# power_electronics4.net
KiCad netlist of a schematic drawn in EAGLE
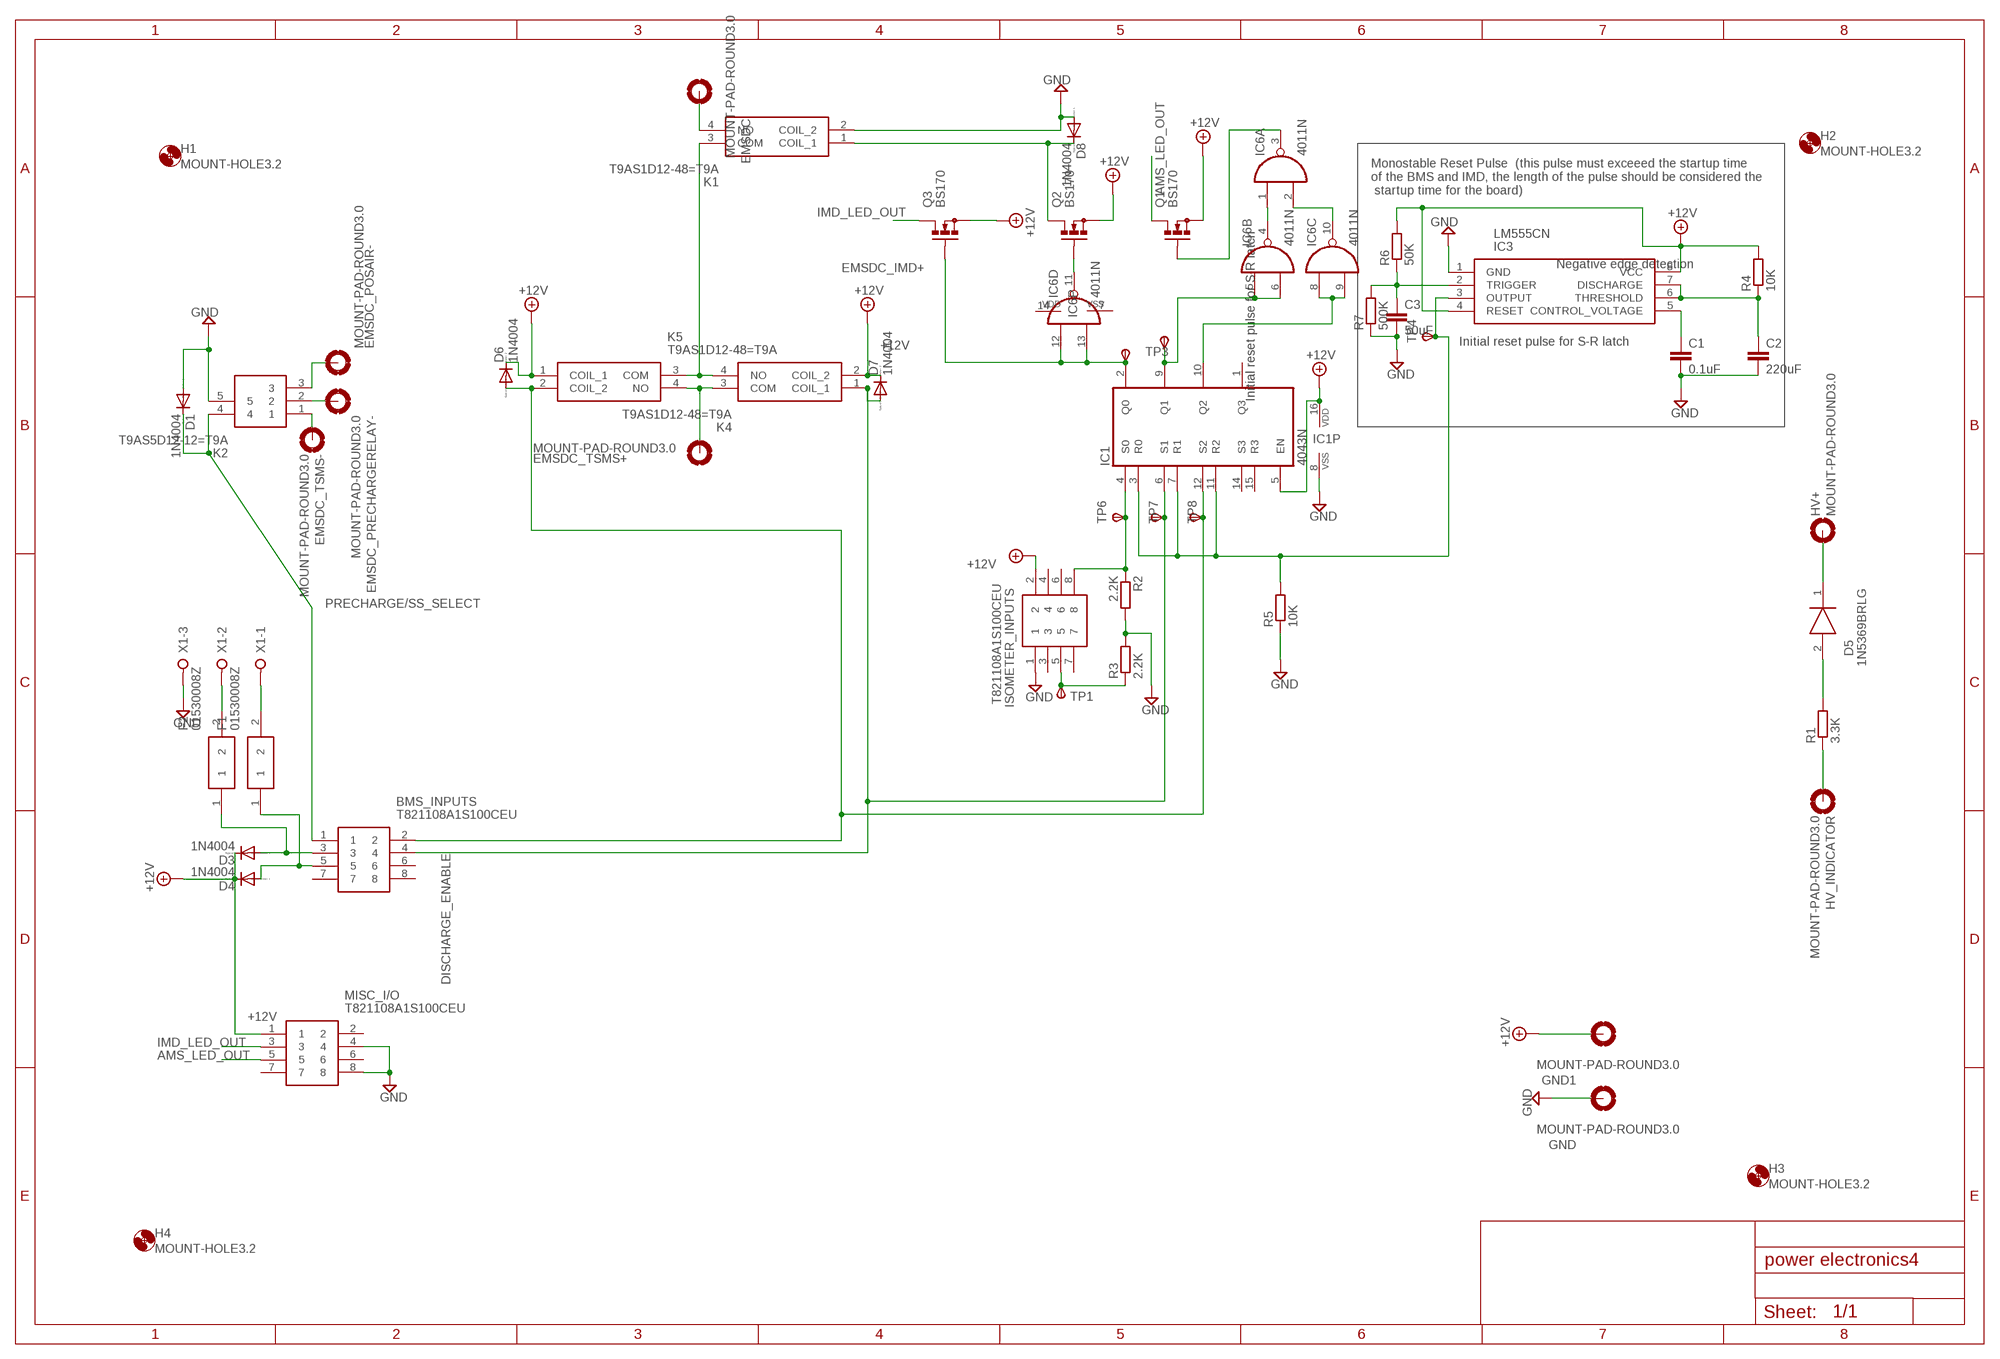
[diagram p0: schematic, sheet 1]

(export (version "E")
  (design (tool "Eeschema 10.0.6"))
  (components
    (comp (ref "BMS_INPUTS")
      (value "T821108A1S100CEU")
      (footprint "eagle-import:HDRV8W64P254_2X4_1778X895X915P")
      (fields (field (name "RS_PART_NUMBER") "8323569"))
      (libsource (lib "eagle-import") (part "T821108A1S100CEU"))
    )
    (comp (ref "C1")
      (value "0.1uF")
      (footprint "eagle-import:C050-024X044")
      (libsource (lib "eagle-import") (part "C-EU050-024X044"))
    )
    (comp (ref "C2")
      (value "220uF")
      (footprint "eagle-import:C050-024X044")
      (libsource (lib "eagle-import") (part "C-EU050-024X044"))
    )
    (comp (ref "C3")
      (value "50uF")
      (footprint "eagle-import:C050-024X044")
      (libsource (lib "eagle-import") (part "C-EU050-024X044"))
    )
    (comp (ref "D1")
      (value "1N4004")
      (footprint "eagle-import:DO41-10")
      (libsource (lib "eagle-import") (part "1N4004"))
    )
    (comp (ref "D3")
      (value "1N4004")
      (footprint "eagle-import:DO41-10")
      (libsource (lib "eagle-import") (part "1N4004"))
    )
    (comp (ref "D4")
      (value "1N4004")
      (footprint "eagle-import:DO41-10")
      (libsource (lib "eagle-import") (part "1N4004"))
    )
    (comp (ref "D5")
      (value "1N5369BRLG")
      (footprint "eagle-import:DIOAD2260W109L864D349")
      (fields (field (name "RS_PART_NUMBER") "6547678P"))
      (libsource (lib "eagle-import") (part "1N5369BRLG"))
    )
    (comp (ref "D6")
      (value "1N4004")
      (footprint "eagle-import:DO41-10")
      (libsource (lib "eagle-import") (part "1N4004"))
    )
    (comp (ref "D7")
      (value "1N4004")
      (footprint "eagle-import:DO41-10")
      (libsource (lib "eagle-import") (part "1N4004"))
    )
    (comp (ref "D8")
      (value "1N4004")
      (footprint "eagle-import:DO41-10")
      (libsource (lib "eagle-import") (part "1N4004"))
    )
    (comp (ref "EMSDC")
      (value "MOUNT-PAD-ROUND3.0")
      (footprint "eagle-import:3,0-PAD")
      (libsource (lib "eagle-import") (part "MOUNT-PAD-ROUND3.0"))
    )
    (comp (ref "EMSDC_POSAIR-")
      (value "MOUNT-PAD-ROUND3.0")
      (footprint "eagle-import:3,0-PAD")
      (libsource (lib "eagle-import") (part "MOUNT-PAD-ROUND3.0"))
    )
    (comp (ref "EMSDC_PRECHARGERELAY-")
      (value "MOUNT-PAD-ROUND3.0")
      (footprint "eagle-import:3,0-PAD")
      (libsource (lib "eagle-import") (part "MOUNT-PAD-ROUND3.0"))
    )
    (comp (ref "EMSDC_TSMS+")
      (value "MOUNT-PAD-ROUND3.0")
      (footprint "eagle-import:3,0-PAD")
      (libsource (lib "eagle-import") (part "MOUNT-PAD-ROUND3.0"))
    )
    (comp (ref "EMSDC_TSMS-")
      (value "MOUNT-PAD-ROUND3.0")
      (footprint "eagle-import:3,0-PAD")
      (libsource (lib "eagle-import") (part "MOUNT-PAD-ROUND3.0"))
    )
    (comp (ref "F1")
      (value "01530008Z")
      (footprint "eagle-import:01530008")
      (fields (field (name "RS_PART_NUMBER") "3607317"))
      (libsource (lib "eagle-import") (part "01530008Z"))
    )
    (comp (ref "F2")
      (value "01530008Z")
      (footprint "eagle-import:01530008")
      (fields (field (name "RS_PART_NUMBER") "3607317"))
      (libsource (lib "eagle-import") (part "01530008Z"))
    )
    (comp (ref "GND")
      (value "MOUNT-PAD-ROUND3.0")
      (footprint "eagle-import:3,0-PAD")
      (libsource (lib "eagle-import") (part "MOUNT-PAD-ROUND3.0"))
    )
    (comp (ref "GND1")
      (value "MOUNT-PAD-ROUND3.0")
      (footprint "eagle-import:3,0-PAD")
      (libsource (lib "eagle-import") (part "MOUNT-PAD-ROUND3.0"))
    )
    (comp (ref "H1")
      (value "MOUNT-HOLE3.2")
      (footprint "eagle-import:3,2")
      (libsource (lib "eagle-import") (part "MOUNT-HOLE3.2"))
    )
    (comp (ref "H2")
      (value "MOUNT-HOLE3.2")
      (footprint "eagle-import:3,2")
      (libsource (lib "eagle-import") (part "MOUNT-HOLE3.2"))
    )
    (comp (ref "H3")
      (value "MOUNT-HOLE3.2")
      (footprint "eagle-import:3,2")
      (libsource (lib "eagle-import") (part "MOUNT-HOLE3.2"))
    )
    (comp (ref "H4")
      (value "MOUNT-HOLE3.2")
      (footprint "eagle-import:3,2")
      (libsource (lib "eagle-import") (part "MOUNT-HOLE3.2"))
    )
    (comp (ref "HV+")
      (value "MOUNT-PAD-ROUND3.0")
      (footprint "eagle-import:3,0-PAD")
      (libsource (lib "eagle-import") (part "MOUNT-PAD-ROUND3.0"))
    )
    (comp (ref "HV_INDICATOR")
      (value "MOUNT-PAD-ROUND3.0")
      (footprint "eagle-import:3,0-PAD")
      (libsource (lib "eagle-import") (part "MOUNT-PAD-ROUND3.0"))
    )
    (comp (ref "IC1")
      (value "4043N")
      (footprint "eagle-import:DIL16")
      (libsource (lib "eagle-import") (part "4043N"))
    )
    (comp (ref "IC3")
      (value "LM555CN")
      (footprint "eagle-import:DIP762W53P254L980H533Q8N")
      (fields (field (name "MOUSER_PART_NUMBER") "512-LM555CN"))
      (libsource (lib "eagle-import") (part "LM555CN"))
    )
    (comp (ref "IC6")
      (value "4011N")
      (footprint "eagle-import:DIL14")
      (libsource (lib "eagle-import") (part "4011N"))
    )
    (comp (ref "ISOMETER_INPUTS")
      (value "T821108A1S100CEU")
      (footprint "eagle-import:HDRV8W64P254_2X4_1778X895X915P")
      (fields (field (name "RS_PART_NUMBER") "8323569"))
      (libsource (lib "eagle-import") (part "T821108A1S100CEU"))
    )
    (comp (ref "K1")
      (value "T9AS1D12-48=T9A")
      (footprint "eagle-import:T9AS1D1248T9A")
      (fields (field (name "RS_PART_NUMBER") "6802534P"))
      (libsource (lib "eagle-import") (part "T9AS1D12-48=T9A"))
    )
    (comp (ref "K2")
      (value "T9AS5D12-12=T9A")
      (footprint "eagle-import:T9AS1D12")
      (fields (field (name "RS_PART_NUMBER") "6802528"))
      (libsource (lib "eagle-import") (part "T9AS5D12-12=T9A"))
    )
    (comp (ref "K4")
      (value "T9AS1D12-48=T9A")
      (footprint "eagle-import:T9AS1D1248T9A")
      (fields (field (name "RS_PART_NUMBER") "6802534P"))
      (libsource (lib "eagle-import") (part "T9AS1D12-48=T9A"))
    )
    (comp (ref "K5")
      (value "T9AS1D12-48=T9A")
      (footprint "eagle-import:T9AS1D1248T9A")
      (fields (field (name "RS_PART_NUMBER") "6802534P"))
      (libsource (lib "eagle-import") (part "T9AS1D12-48=T9A"))
    )
    (comp (ref "MISC_I/O")
      (value "T821108A1S100CEU")
      (footprint "eagle-import:HDRV8W64P254_2X4_1778X895X915P")
      (fields (field (name "RS_PART_NUMBER") "8323569"))
      (libsource (lib "eagle-import") (part "T821108A1S100CEU"))
    )
    (comp (ref "Q1")
      (value "BS170")
      (footprint "eagle-import:SOT54E")
      (libsource (lib "eagle-import") (part "BS170"))
    )
    (comp (ref "Q2")
      (value "BS170")
      (footprint "eagle-import:SOT54E")
      (libsource (lib "eagle-import") (part "BS170"))
    )
    (comp (ref "Q3")
      (value "BS170")
      (footprint "eagle-import:SOT54E")
      (libsource (lib "eagle-import") (part "BS170"))
    )
    (comp (ref "R1")
      (value "3.3K")
      (footprint "eagle-import:0207_15")
      (libsource (lib "eagle-import") (part "R-EU_0207/15"))
    )
    (comp (ref "R2")
      (value "2.2K")
      (footprint "eagle-import:0207_12")
      (libsource (lib "eagle-import") (part "R-EU_0207/12"))
    )
    (comp (ref "R3")
      (value "2.2K")
      (footprint "eagle-import:0207_12")
      (libsource (lib "eagle-import") (part "R-EU_0207/12"))
    )
    (comp (ref "R4")
      (value "10K")
      (footprint "eagle-import:0207_15")
      (libsource (lib "eagle-import") (part "R-EU_0207/15"))
    )
    (comp (ref "R5")
      (value "10K")
      (footprint "eagle-import:0207_15")
      (libsource (lib "eagle-import") (part "R-EU_0207/15"))
    )
    (comp (ref "R6")
      (value "50K")
      (footprint "eagle-import:0207_15")
      (libsource (lib "eagle-import") (part "R-EU_0207/15"))
    )
    (comp (ref "R7")
      (value "500K")
      (footprint "eagle-import:0207_15")
      (libsource (lib "eagle-import") (part "R-EU_0207/15"))
    )
    (comp (ref "TP1")
      (value "TPSPAD1-17")
      (footprint "eagle-import:P1-17")
      (libsource (lib "eagle-import") (part "TPSPAD1-17"))
    )
    (comp (ref "TP2")
      (value "TPSPAD1-17")
      (footprint "eagle-import:P1-17")
      (libsource (lib "eagle-import") (part "TPSPAD1-17"))
    )
    (comp (ref "TP3")
      (value "TPSPAD1-17")
      (footprint "eagle-import:P1-17")
      (libsource (lib "eagle-import") (part "TPSPAD1-17"))
    )
    (comp (ref "TP4")
      (value "TPSPAD1-17")
      (footprint "eagle-import:P1-17")
      (libsource (lib "eagle-import") (part "TPSPAD1-17"))
    )
    (comp (ref "TP6")
      (value "TPSPAD1-17")
      (footprint "eagle-import:P1-17")
      (libsource (lib "eagle-import") (part "TPSPAD1-17"))
    )
    (comp (ref "TP7")
      (value "TPSPAD1-17")
      (footprint "eagle-import:P1-17")
      (libsource (lib "eagle-import") (part "TPSPAD1-17"))
    )
    (comp (ref "TP8")
      (value "TPSPAD1-17")
      (footprint "eagle-import:P1-17")
      (libsource (lib "eagle-import") (part "TPSPAD1-17"))
    )
    (comp (ref "X1")
      (value "W237-3E")
      (footprint "eagle-import:W237-3E")
      (libsource (lib "eagle-import") (part "W237-3E"))
    )
  )
  (nets
    (net (code "1") (name "+12V") (class "Default")
      (node (ref "D3") (pin "C") (pinfunction "C_C") (pintype "passive"))
      (node (ref "D4") (pin "C") (pinfunction "C_C") (pintype "passive"))
      (node (ref "D6") (pin "C") (pinfunction "C_C") (pintype "passive"))
      (node (ref "D7") (pin "C") (pinfunction "C_C") (pintype "passive"))
      (node (ref "GND1") (pin "B3,0") (pinfunction "MOUNT_B3,0") (pintype "passive"))
      (node (ref "IC1") (pin "16") (pinfunction "VDD_16") (pintype "power_in"))
      (node (ref "IC1") (pin "5") (pinfunction "EN_5") (pintype "input"))
      (node (ref "IC3") (pin "4") (pinfunction "RESET_4") (pintype "bidirectional"))
      (node (ref "IC3") (pin "8") (pinfunction "VCC_8") (pintype "bidirectional"))
      (node (ref "ISOMETER_INPUTS") (pin "2") (pinfunction "2_2") (pintype "bidirectional"))
      (node (ref "K4") (pin "2") (pinfunction "COIL_2_2") (pintype "bidirectional"))
      (node (ref "K5") (pin "1") (pinfunction "COIL_1_1") (pintype "bidirectional"))
      (node (ref "MISC_I/O") (pin "1") (pinfunction "1_1") (pintype "bidirectional"))
      (node (ref "Q1") (pin "S") (pinfunction "S_S") (pintype "passive"))
      (node (ref "Q2") (pin "S") (pinfunction "S_S") (pintype "passive"))
      (node (ref "Q3") (pin "S") (pinfunction "S_S") (pintype "passive"))
      (node (ref "R4") (pin "2") (pinfunction "2_2") (pintype "passive"))
      (node (ref "R6") (pin "2") (pinfunction "2_2") (pintype "passive"))
    )
    (net (code "2") (name "/AMS_LED_OUT") (class "Default")
      (node (ref "MISC_I/O") (pin "5") (pinfunction "5_5") (pintype "bidirectional"))
      (node (ref "Q1") (pin "D") (pinfunction "D_D") (pintype "passive"))
    )
    (net (code "3") (name "/DISCHARGE_ENABLE") (class "Default")
      (node (ref "BMS_INPUTS") (pin "4") (pinfunction "4_4") (pintype "bidirectional"))
      (node (ref "D7") (pin "A") (pinfunction "A_A") (pintype "passive"))
      (node (ref "IC1") (pin "6") (pinfunction "S1_6") (pintype "input"))
      (node (ref "K4") (pin "1") (pinfunction "COIL_1_1") (pintype "bidirectional"))
      (node (ref "TP7") (pin "TP") (pinfunction "PP_TP") (pintype "input"))
    )
    (net (code "4") (name "/EMSDC_IMD+") (class "Default")
      (node (ref "K1") (pin "3") (pinfunction "COM_3") (pintype "bidirectional"))
      (node (ref "K4") (pin "4") (pinfunction "NO_4") (pintype "bidirectional"))
      (node (ref "K5") (pin "3") (pinfunction "COM_3") (pintype "bidirectional"))
    )
    (net (code "5") (name "/IMD_LED_OUT") (class "Default")
      (node (ref "MISC_I/O") (pin "3") (pinfunction "3_3") (pintype "bidirectional"))
      (node (ref "Q3") (pin "D") (pinfunction "D_D") (pintype "passive"))
    )
    (net (code "6") (name "/PRECHARGE{slash}SS_SELECT") (class "Default")
      (node (ref "BMS_INPUTS") (pin "1") (pinfunction "1_1") (pintype "bidirectional"))
      (node (ref "D1") (pin "C") (pinfunction "C_C") (pintype "passive"))
      (node (ref "K2") (pin "4") (pinfunction "4_4") (pintype "bidirectional"))
    )
    (net (code "7") (name "/VDD") (class "Default")
      (node (ref "IC6") (pin "14") (pinfunction "VDD_14") (pintype "power_in"))
    )
    (net (code "8") (name "/VSS") (class "Default")
      (node (ref "IC6") (pin "7") (pinfunction "VSS_7") (pintype "power_in"))
    )
    (net (code "9") (name "GND") (class "Default")
      (node (ref "C1") (pin "2") (pinfunction "2_2") (pintype "passive"))
      (node (ref "C2") (pin "2") (pinfunction "2_2") (pintype "passive"))
      (node (ref "C3") (pin "2") (pinfunction "2_2") (pintype "passive"))
      (node (ref "D1") (pin "A") (pinfunction "A_A") (pintype "passive"))
      (node (ref "D8") (pin "A") (pinfunction "A_A") (pintype "passive"))
      (node (ref "GND") (pin "B3,0") (pinfunction "MOUNT_B3,0") (pintype "passive"))
      (node (ref "IC1") (pin "8") (pinfunction "VSS_8") (pintype "power_in"))
      (node (ref "IC3") (pin "1") (pinfunction "GND_1") (pintype "bidirectional"))
      (node (ref "ISOMETER_INPUTS") (pin "1") (pinfunction "1_1") (pintype "bidirectional"))
      (node (ref "K1") (pin "2") (pinfunction "COIL_2_2") (pintype "bidirectional"))
      (node (ref "K2") (pin "5") (pinfunction "5_5") (pintype "bidirectional"))
      (node (ref "MISC_I/O") (pin "4") (pinfunction "4_4") (pintype "bidirectional"))
      (node (ref "MISC_I/O") (pin "8") (pinfunction "8_8") (pintype "bidirectional"))
      (node (ref "R2") (pin "2") (pinfunction "2_2") (pintype "passive"))
      (node (ref "R3") (pin "2") (pinfunction "2_2") (pintype "passive"))
      (node (ref "R5") (pin "1") (pinfunction "1_1") (pintype "passive"))
      (node (ref "R7") (pin "1") (pinfunction "1_1") (pintype "passive"))
      (node (ref "X1") (pin "3") (pinfunction "KL_3") (pintype "passive"))
    )
    (net (code "10") (name "Net-(BMS_INPUTS-Pad3)") (class "Default")
      (node (ref "BMS_INPUTS") (pin "3") (pinfunction "3_3") (pintype "bidirectional"))
      (node (ref "D3") (pin "A") (pinfunction "A_A") (pintype "passive"))
      (node (ref "F2") (pin "1") (pinfunction "1_1") (pintype "bidirectional"))
    )
    (net (code "11") (name "Net-(BMS_INPUTS-Pad5)") (class "Default")
      (node (ref "BMS_INPUTS") (pin "5") (pinfunction "5_5") (pintype "bidirectional"))
      (node (ref "D4") (pin "A") (pinfunction "A_A") (pintype "passive"))
      (node (ref "F1") (pin "1") (pinfunction "1_1") (pintype "bidirectional"))
    )
    (net (code "12") (name "Net-(D5-A)") (class "Default")
      (node (ref "D5") (pin "2") (pinfunction "A_2") (pintype "bidirectional"))
      (node (ref "R1") (pin "2") (pinfunction "2_2") (pintype "passive"))
    )
    (net (code "13") (name "Net-(D5-K)") (class "Default")
      (node (ref "D5") (pin "1") (pinfunction "K_1") (pintype "bidirectional"))
      (node (ref "HV+") (pin "B3,0") (pinfunction "MOUNT_B3,0") (pintype "passive"))
    )
    (net (code "14") (name "Net-(EMSDC-MOUNT)") (class "Default")
      (node (ref "EMSDC") (pin "B3,0") (pinfunction "MOUNT_B3,0") (pintype "passive"))
      (node (ref "K1") (pin "4") (pinfunction "NO_4") (pintype "bidirectional"))
    )
    (net (code "15") (name "Net-(EMSDC_POSAIR--MOUNT)") (class "Default")
      (node (ref "EMSDC_POSAIR-") (pin "B3,0") (pinfunction "MOUNT_B3,0") (pintype "passive"))
      (node (ref "K2") (pin "3") (pinfunction "3_3") (pintype "bidirectional"))
    )
    (net (code "16") (name "Net-(EMSDC_PRECHARGERELAY--MOUNT)") (class "Default")
      (node (ref "EMSDC_PRECHARGERELAY-") (pin "B3,0") (pinfunction "MOUNT_B3,0") (pintype "passive"))
      (node (ref "K2") (pin "2") (pinfunction "2_2") (pintype "bidirectional"))
    )
    (net (code "17") (name "Net-(EMSDC_TSMS+-MOUNT)") (class "Default")
      (node (ref "EMSDC_TSMS+") (pin "B3,0") (pinfunction "MOUNT_B3,0") (pintype "passive"))
      (node (ref "K4") (pin "3") (pinfunction "COM_3") (pintype "bidirectional"))
      (node (ref "K5") (pin "4") (pinfunction "NO_4") (pintype "bidirectional"))
    )
    (net (code "18") (name "Net-(EMSDC_TSMS--MOUNT)") (class "Default")
      (node (ref "EMSDC_TSMS-") (pin "B3,0") (pinfunction "MOUNT_B3,0") (pintype "passive"))
      (node (ref "K2") (pin "1") (pinfunction "1_1") (pintype "bidirectional"))
    )
    (net (code "19") (name "Net-(HV_INDICATOR-MOUNT)") (class "Default")
      (node (ref "HV_INDICATOR") (pin "B3,0") (pinfunction "MOUNT_B3,0") (pintype "passive"))
      (node (ref "R1") (pin "1") (pinfunction "1_1") (pintype "passive"))
    )
    (net (code "20") (name "Net-(IC1A-Q0)") (class "Default")
      (node (ref "IC1") (pin "2") (pinfunction "Q0_2") (pintype "output"))
      (node (ref "IC6") (pin "12") (pinfunction "I0_12") (pintype "input"))
      (node (ref "IC6") (pin "13") (pinfunction "I1_13") (pintype "input"))
      (node (ref "Q3") (pin "G") (pinfunction "G_G") (pintype "passive"))
      (node (ref "TP2") (pin "TP") (pinfunction "PP_TP") (pintype "input"))
    )
    (net (code "21") (name "Net-(IC1A-Q1)") (class "Default")
      (node (ref "IC1") (pin "9") (pinfunction "Q1_9") (pintype "output"))
      (node (ref "IC6") (pin "5") (pinfunction "I0_5") (pintype "input"))
      (node (ref "IC6") (pin "6") (pinfunction "I1_6") (pintype "input"))
      (node (ref "TP3") (pin "TP") (pinfunction "PP_TP") (pintype "input"))
    )
    (net (code "22") (name "Net-(IC1A-Q2)") (class "Default")
      (node (ref "IC1") (pin "10") (pinfunction "Q2_10") (pintype "output"))
      (node (ref "IC6") (pin "8") (pinfunction "I0_8") (pintype "input"))
      (node (ref "IC6") (pin "9") (pinfunction "I1_9") (pintype "input"))
    )
    (net (code "23") (name "Net-(IC1A-R0)") (class "Default")
      (node (ref "IC1") (pin "11") (pinfunction "R2_11") (pintype "input"))
      (node (ref "IC1") (pin "3") (pinfunction "R0_3") (pintype "input"))
      (node (ref "IC1") (pin "7") (pinfunction "R1_7") (pintype "input"))
      (node (ref "IC3") (pin "3") (pinfunction "OUTPUT_3") (pintype "bidirectional"))
      (node (ref "R5") (pin "2") (pinfunction "2_2") (pintype "passive"))
      (node (ref "TP4") (pin "TP") (pinfunction "PP_TP") (pintype "input"))
    )
    (net (code "24") (name "Net-(IC1A-S0)") (class "Default")
      (node (ref "IC1") (pin "4") (pinfunction "S0_4") (pintype "input"))
      (node (ref "ISOMETER_INPUTS") (pin "8") (pinfunction "8_8") (pintype "bidirectional"))
      (node (ref "R2") (pin "1") (pinfunction "1_1") (pintype "passive"))
      (node (ref "TP6") (pin "TP") (pinfunction "PP_TP") (pintype "input"))
    )
    (net (code "25") (name "Net-(IC1A-S2)") (class "Default")
      (node (ref "BMS_INPUTS") (pin "2") (pinfunction "2_2") (pintype "bidirectional"))
      (node (ref "D6") (pin "A") (pinfunction "A_A") (pintype "passive"))
      (node (ref "IC1") (pin "12") (pinfunction "S2_12") (pintype "input"))
      (node (ref "K5") (pin "2") (pinfunction "COIL_2_2") (pintype "bidirectional"))
      (node (ref "TP8") (pin "TP") (pinfunction "PP_TP") (pintype "input"))
    )
    (net (code "26") (name "Net-(IC3-CONTROL_VOLTAGE)") (class "Default")
      (node (ref "C1") (pin "1") (pinfunction "1_1") (pintype "passive"))
      (node (ref "IC3") (pin "5") (pinfunction "CONTROL_VOLTAGE_5") (pintype "bidirectional"))
    )
    (net (code "27") (name "Net-(IC3-DISCHARGE)") (class "Default")
      (node (ref "C2") (pin "1") (pinfunction "1_1") (pintype "passive"))
      (node (ref "IC3") (pin "6") (pinfunction "THRESHOLD_6") (pintype "bidirectional"))
      (node (ref "IC3") (pin "7") (pinfunction "DISCHARGE_7") (pintype "bidirectional"))
      (node (ref "R4") (pin "1") (pinfunction "1_1") (pintype "passive"))
    )
    (net (code "28") (name "Net-(IC3-TRIGGER)") (class "Default")
      (node (ref "C3") (pin "1") (pinfunction "1_1") (pintype "passive"))
      (node (ref "IC3") (pin "2") (pinfunction "TRIGGER_2") (pintype "bidirectional"))
      (node (ref "R6") (pin "1") (pinfunction "1_1") (pintype "passive"))
      (node (ref "R7") (pin "2") (pinfunction "2_2") (pintype "passive"))
    )
    (net (code "29") (name "Net-(IC6A-I0)") (class "Default")
      (node (ref "IC6") (pin "1") (pinfunction "I0_1") (pintype "input"))
      (node (ref "IC6") (pin "4") (pinfunction "O_4") (pintype "output"))
    )
    (net (code "30") (name "Net-(IC6A-I1)") (class "Default")
      (node (ref "IC6") (pin "10") (pinfunction "O_10") (pintype "output"))
      (node (ref "IC6") (pin "2") (pinfunction "I1_2") (pintype "input"))
    )
    (net (code "31") (name "Net-(IC6A-O)") (class "Default")
      (node (ref "IC6") (pin "3") (pinfunction "O_3") (pintype "output"))
      (node (ref "Q1") (pin "G") (pinfunction "G_G") (pintype "passive"))
    )
    (net (code "32") (name "Net-(IC6D-O)") (class "Default")
      (node (ref "IC6") (pin "11") (pinfunction "O_11") (pintype "output"))
      (node (ref "Q2") (pin "G") (pinfunction "G_G") (pintype "passive"))
    )
    (net (code "33") (name "Net-(K1-COIL_1)") (class "Default")
      (node (ref "D8") (pin "C") (pinfunction "C_C") (pintype "passive"))
      (node (ref "K1") (pin "1") (pinfunction "COIL_1_1") (pintype "bidirectional"))
      (node (ref "Q2") (pin "D") (pinfunction "D_D") (pintype "passive"))
    )
    (net (code "34") (name "Net-(TP1-PP)") (class "Default")
      (node (ref "ISOMETER_INPUTS") (pin "5") (pinfunction "5_5") (pintype "bidirectional"))
      (node (ref "R3") (pin "1") (pinfunction "1_1") (pintype "passive"))
      (node (ref "TP1") (pin "TP") (pinfunction "PP_TP") (pintype "input"))
    )
    (net (code "35") (name "Net-(X1A-KL)") (class "Default")
      (node (ref "F1") (pin "2") (pinfunction "2_2") (pintype "bidirectional"))
      (node (ref "X1") (pin "1") (pinfunction "KL_1") (pintype "passive"))
    )
    (net (code "36") (name "Net-(X1B-KL)") (class "Default")
      (node (ref "F2") (pin "2") (pinfunction "2_2") (pintype "bidirectional"))
      (node (ref "X1") (pin "2") (pinfunction "KL_2") (pintype "passive"))
    )
    (net (code "37") (name "unconnected-(BMS_INPUTS-Pad6)") (class "Default")
      (node (ref "BMS_INPUTS") (pin "6") (pinfunction "6_6") (pintype "bidirectional"))
    )
    (net (code "38") (name "unconnected-(BMS_INPUTS-Pad7)") (class "Default")
      (node (ref "BMS_INPUTS") (pin "7") (pinfunction "7_7") (pintype "bidirectional"))
    )
    (net (code "39") (name "unconnected-(BMS_INPUTS-Pad8)") (class "Default")
      (node (ref "BMS_INPUTS") (pin "8") (pinfunction "8_8") (pintype "bidirectional"))
    )
    (net (code "40") (name "unconnected-(IC1A-Q3-Pad1)") (class "Default")
      (node (ref "IC1") (pin "1") (pinfunction "Q3_1") (pintype "output"))
    )
    (net (code "41") (name "unconnected-(IC1A-R3-Pad15)") (class "Default")
      (node (ref "IC1") (pin "15") (pinfunction "R3_15") (pintype "input"))
    )
    (net (code "42") (name "unconnected-(IC1A-S3-Pad14)") (class "Default")
      (node (ref "IC1") (pin "14") (pinfunction "S3_14") (pintype "input"))
    )
    (net (code "43") (name "unconnected-(ISOMETER_INPUTS-Pad3)") (class "Default")
      (node (ref "ISOMETER_INPUTS") (pin "3") (pinfunction "3_3") (pintype "bidirectional"))
    )
    (net (code "44") (name "unconnected-(ISOMETER_INPUTS-Pad4)") (class "Default")
      (node (ref "ISOMETER_INPUTS") (pin "4") (pinfunction "4_4") (pintype "bidirectional"))
    )
    (net (code "45") (name "unconnected-(ISOMETER_INPUTS-Pad6)") (class "Default")
      (node (ref "ISOMETER_INPUTS") (pin "6") (pinfunction "6_6") (pintype "bidirectional"))
    )
    (net (code "46") (name "unconnected-(ISOMETER_INPUTS-Pad7)") (class "Default")
      (node (ref "ISOMETER_INPUTS") (pin "7") (pinfunction "7_7") (pintype "bidirectional"))
    )
    (net (code "47") (name "unconnected-(MISC_I/O-Pad2)") (class "Default")
      (node (ref "MISC_I/O") (pin "2") (pinfunction "2_2") (pintype "bidirectional"))
    )
    (net (code "48") (name "unconnected-(MISC_I/O-Pad6)") (class "Default")
      (node (ref "MISC_I/O") (pin "6") (pinfunction "6_6") (pintype "bidirectional"))
    )
    (net (code "49") (name "unconnected-(MISC_I/O-Pad7)") (class "Default")
      (node (ref "MISC_I/O") (pin "7") (pinfunction "7_7") (pintype "bidirectional"))
    )
  )
)
